# ESP32FishLightBoard.net
KiCad netlist of a schematic drawn in EAGLE
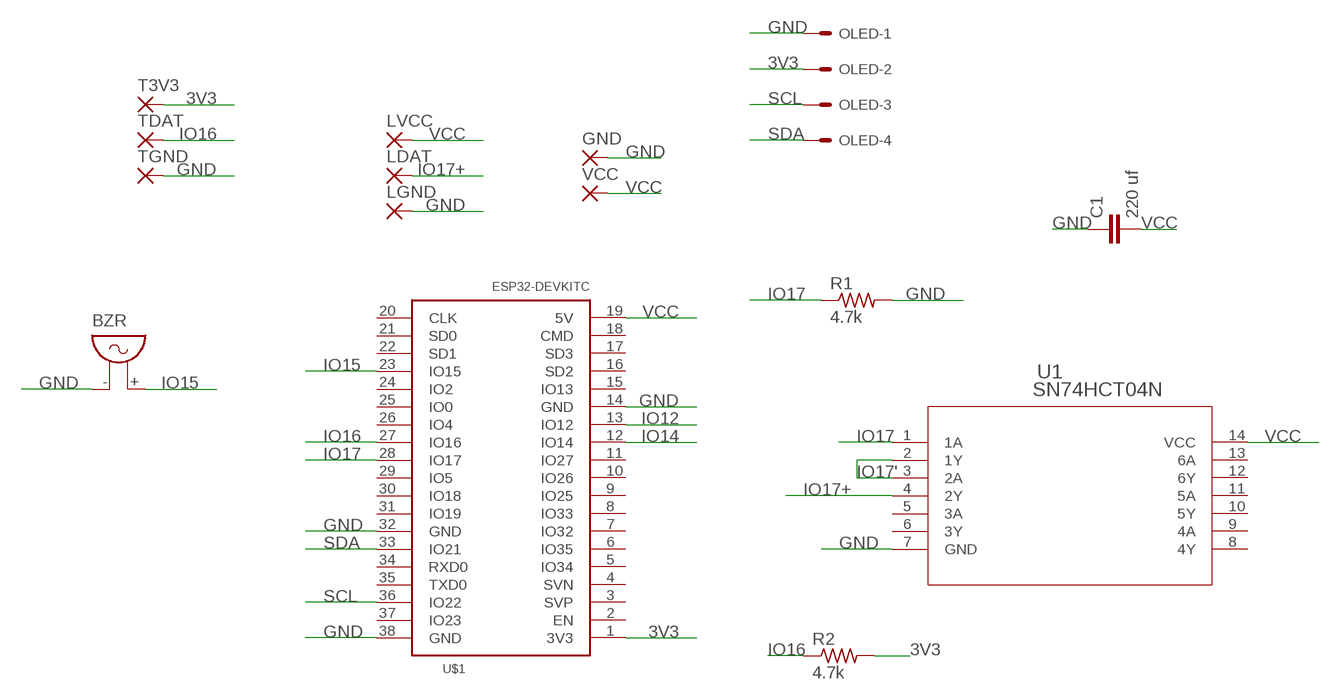
[diagram p0: schematic, sheet 1]

(export (version "E")
  (design (tool "Eeschema 10.0.6"))
  (components
    (comp (ref "BZR")
      (value "F/QMX")
      (footprint "eagle-import:F_QMX")
      (libsource (lib "eagle-import") (part "F/QMX"))
    )
    (comp (ref "C1")
      (value "220 uf")
      (footprint "eagle-import:C2.5-3")
      (libsource (lib "eagle-import") (part "C2,5-3"))
    )
    (comp (ref "GND")
      (value "WIREPAD2,54/1,0")
      (footprint "eagle-import:2,54_1,0")
      (libsource (lib "eagle-import") (part "WIREPAD2,54/1,0"))
    )
    (comp (ref "LDAT")
      (value "WIREPAD2,54/1,0")
      (footprint "eagle-import:2,54_1,0")
      (libsource (lib "eagle-import") (part "WIREPAD2,54/1,0"))
    )
    (comp (ref "LGND")
      (value "WIREPAD2,54/1,0")
      (footprint "eagle-import:2,54_1,0")
      (libsource (lib "eagle-import") (part "WIREPAD2,54/1,0"))
    )
    (comp (ref "LVCC")
      (value "WIREPAD2,54/1,0")
      (footprint "eagle-import:2,54_1,0")
      (libsource (lib "eagle-import") (part "WIREPAD2,54/1,0"))
    )
    (comp (ref "OLED")
      (value "22-27-2041-04")
      (footprint "eagle-import:6410-04")
      (fields (field (name "MF") "MOLEX"))
      (libsource (lib "eagle-import") (part "22-?-0427-2041"))
    )
    (comp (ref "R1")
      (value "4.7k")
      (footprint "eagle-import:0805-THM")
      (libsource (lib "eagle-import") (part "FLIPFLOP-RES"))
    )
    (comp (ref "R2")
      (value "4.7k")
      (footprint "eagle-import:0805-THM")
      (libsource (lib "eagle-import") (part "FLIPFLOP-RES"))
    )
    (comp (ref "T3V3")
      (value "WIREPAD2,54/1,0")
      (footprint "eagle-import:2,54_1,0")
      (libsource (lib "eagle-import") (part "WIREPAD2,54/1,0"))
    )
    (comp (ref "TDAT")
      (value "WIREPAD2,54/1,0")
      (footprint "eagle-import:2,54_1,0")
      (libsource (lib "eagle-import") (part "WIREPAD2,54/1,0"))
    )
    (comp (ref "TGND")
      (value "WIREPAD2,54/1,0")
      (footprint "eagle-import:2,54_1,0")
      (libsource (lib "eagle-import") (part "WIREPAD2,54/1,0"))
    )
    (comp (ref "U$1")
      (value "ESP32DEVKITC-LIGHT")
      (footprint "eagle-import:ESP32-DEVKITC-LIGHT")
      (libsource (lib "eagle-import") (part "ESP32DEVKITC-LIGHT"))
    )
    (comp (ref "U1")
      (value "SN74HCT04N")
      (footprint "eagle-import:N14")
      (fields
        (field (name "GENERIC_PART_NUMBER") "SN74HCT04")
        (field (name "MANUFACTURER") "Texas Instruments")
      )
      (libsource (lib "eagle-import") (part "SN74HCT04N"))
    )
    (comp (ref "VCC")
      (value "WIREPAD2,54/1,0")
      (footprint "eagle-import:2,54_1,0")
      (libsource (lib "eagle-import") (part "WIREPAD2,54/1,0"))
    )
  )
  (nets
    (net (code "1") (name "/3V3") (class "Default")
      (node (ref "OLED") (pin "2") (pinfunction "S_2") (pintype "passive"))
      (node (ref "R2") (pin "2") (pinfunction "2_2") (pintype "passive"))
      (node (ref "T3V3") (pin "1") (pinfunction "P_1") (pintype "passive"))
      (node (ref "U$1") (pin "1") (pinfunction "3V3_1") (pintype "bidirectional"))
    )
    (net (code "2") (name "/GND") (class "Default")
      (node (ref "BZR") (pin "-") (pinfunction "1_-") (pintype "passive"))
      (node (ref "C1") (pin "1") (pinfunction "1_1") (pintype "passive"))
      (node (ref "GND") (pin "1") (pinfunction "P_1") (pintype "passive"))
      (node (ref "LGND") (pin "1") (pinfunction "P_1") (pintype "passive"))
      (node (ref "OLED") (pin "1") (pinfunction "S_1") (pintype "passive"))
      (node (ref "R1") (pin "2") (pinfunction "2_2") (pintype "passive"))
      (node (ref "TGND") (pin "1") (pinfunction "P_1") (pintype "passive"))
      (node (ref "U$1") (pin "14") (pinfunction "GND_14") (pintype "bidirectional"))
      (node (ref "U$1") (pin "32") (pinfunction "GND_32") (pintype "bidirectional"))
      (node (ref "U$1") (pin "38") (pinfunction "GND_38") (pintype "bidirectional"))
      (node (ref "U1") (pin "7") (pinfunction "GND_7") (pintype "power_in"))
    )
    (net (code "3") (name "/IO12") (class "Default")
      (node (ref "U$1") (pin "13") (pinfunction "IO12_13") (pintype "bidirectional"))
    )
    (net (code "4") (name "/IO14") (class "Default")
      (node (ref "U$1") (pin "12") (pinfunction "IO14_12") (pintype "bidirectional"))
    )
    (net (code "5") (name "/IO15") (class "Default")
      (node (ref "BZR") (pin "+") (pinfunction "2_+") (pintype "passive"))
      (node (ref "U$1") (pin "23") (pinfunction "IO15_23") (pintype "bidirectional"))
    )
    (net (code "6") (name "/IO16") (class "Default")
      (node (ref "R2") (pin "1") (pinfunction "1_1") (pintype "passive"))
      (node (ref "TDAT") (pin "1") (pinfunction "P_1") (pintype "passive"))
      (node (ref "U$1") (pin "27") (pinfunction "IO16_27") (pintype "bidirectional"))
    )
    (net (code "7") (name "/IO17") (class "Default")
      (node (ref "R1") (pin "1") (pinfunction "1_1") (pintype "passive"))
      (node (ref "U$1") (pin "28") (pinfunction "IO17_28") (pintype "bidirectional"))
      (node (ref "U1") (pin "1") (pinfunction "1A_1") (pintype "input"))
    )
    (net (code "8") (name "/IO17'") (class "Default")
      (node (ref "U1") (pin "2") (pinfunction "1Y_2") (pintype "output"))
      (node (ref "U1") (pin "3") (pinfunction "2A_3") (pintype "input"))
    )
    (net (code "9") (name "/IO17+") (class "Default")
      (node (ref "LDAT") (pin "1") (pinfunction "P_1") (pintype "passive"))
      (node (ref "U1") (pin "4") (pinfunction "2Y_4") (pintype "output"))
    )
    (net (code "10") (name "/SCL") (class "Default")
      (node (ref "OLED") (pin "3") (pinfunction "S_3") (pintype "passive"))
      (node (ref "U$1") (pin "36") (pinfunction "IO22_36") (pintype "bidirectional"))
    )
    (net (code "11") (name "/SDA") (class "Default")
      (node (ref "OLED") (pin "4") (pinfunction "S_4") (pintype "passive"))
      (node (ref "U$1") (pin "33") (pinfunction "IO21_33") (pintype "bidirectional"))
    )
    (net (code "12") (name "/VCC") (class "Default")
      (node (ref "C1") (pin "2") (pinfunction "2_2") (pintype "passive"))
      (node (ref "LVCC") (pin "1") (pinfunction "P_1") (pintype "passive"))
      (node (ref "U$1") (pin "19") (pinfunction "5V_19") (pintype "bidirectional"))
      (node (ref "U1") (pin "14") (pinfunction "VCC_14") (pintype "power_in"))
      (node (ref "VCC") (pin "1") (pinfunction "P_1") (pintype "passive"))
    )
    (net (code "13") (name "unconnected-(U$1-CLK-Pad20)") (class "Default")
      (node (ref "U$1") (pin "20") (pinfunction "CLK_20") (pintype "bidirectional"))
    )
    (net (code "14") (name "unconnected-(U$1-CMD-Pad18)") (class "Default")
      (node (ref "U$1") (pin "18") (pinfunction "CMD_18") (pintype "bidirectional"))
    )
    (net (code "15") (name "unconnected-(U$1-EN-Pad2)") (class "Default")
      (node (ref "U$1") (pin "2") (pinfunction "EN_2") (pintype "bidirectional"))
    )
    (net (code "16") (name "unconnected-(U$1-IO0-Pad25)") (class "Default")
      (node (ref "U$1") (pin "25") (pinfunction "IO0_25") (pintype "bidirectional"))
    )
    (net (code "17") (name "unconnected-(U$1-IO2-Pad24)") (class "Default")
      (node (ref "U$1") (pin "24") (pinfunction "IO2_24") (pintype "bidirectional"))
    )
    (net (code "18") (name "unconnected-(U$1-IO4-Pad26)") (class "Default")
      (node (ref "U$1") (pin "26") (pinfunction "IO4_26") (pintype "bidirectional"))
    )
    (net (code "19") (name "unconnected-(U$1-IO5-Pad29)") (class "Default")
      (node (ref "U$1") (pin "29") (pinfunction "IO5_29") (pintype "bidirectional"))
    )
    (net (code "20") (name "unconnected-(U$1-IO13-Pad15)") (class "Default")
      (node (ref "U$1") (pin "15") (pinfunction "IO13_15") (pintype "bidirectional"))
    )
    (net (code "21") (name "unconnected-(U$1-IO18-Pad30)") (class "Default")
      (node (ref "U$1") (pin "30") (pinfunction "IO18_30") (pintype "bidirectional"))
    )
    (net (code "22") (name "unconnected-(U$1-IO19-Pad31)") (class "Default")
      (node (ref "U$1") (pin "31") (pinfunction "IO19_31") (pintype "bidirectional"))
    )
    (net (code "23") (name "unconnected-(U$1-IO23-Pad37)") (class "Default")
      (node (ref "U$1") (pin "37") (pinfunction "IO23_37") (pintype "bidirectional"))
    )
    (net (code "24") (name "unconnected-(U$1-IO25-Pad9)") (class "Default")
      (node (ref "U$1") (pin "9") (pinfunction "IO25_9") (pintype "bidirectional"))
    )
    (net (code "25") (name "unconnected-(U$1-IO26-Pad10)") (class "Default")
      (node (ref "U$1") (pin "10") (pinfunction "IO26_10") (pintype "bidirectional"))
    )
    (net (code "26") (name "unconnected-(U$1-IO27-Pad11)") (class "Default")
      (node (ref "U$1") (pin "11") (pinfunction "IO27_11") (pintype "bidirectional"))
    )
    (net (code "27") (name "unconnected-(U$1-IO32-Pad7)") (class "Default")
      (node (ref "U$1") (pin "7") (pinfunction "IO32_7") (pintype "bidirectional"))
    )
    (net (code "28") (name "unconnected-(U$1-IO33-Pad8)") (class "Default")
      (node (ref "U$1") (pin "8") (pinfunction "IO33_8") (pintype "bidirectional"))
    )
    (net (code "29") (name "unconnected-(U$1-IO34-Pad5)") (class "Default")
      (node (ref "U$1") (pin "5") (pinfunction "IO34_5") (pintype "bidirectional"))
    )
    (net (code "30") (name "unconnected-(U$1-IO35-Pad6)") (class "Default")
      (node (ref "U$1") (pin "6") (pinfunction "IO35_6") (pintype "bidirectional"))
    )
    (net (code "31") (name "unconnected-(U$1-RXD0-Pad34)") (class "Default")
      (node (ref "U$1") (pin "34") (pinfunction "RXD0_34") (pintype "bidirectional"))
    )
    (net (code "32") (name "unconnected-(U$1-SD0-Pad21)") (class "Default")
      (node (ref "U$1") (pin "21") (pinfunction "SD0_21") (pintype "bidirectional"))
    )
    (net (code "33") (name "unconnected-(U$1-SD1-Pad22)") (class "Default")
      (node (ref "U$1") (pin "22") (pinfunction "SD1_22") (pintype "bidirectional"))
    )
    (net (code "34") (name "unconnected-(U$1-SD2-Pad16)") (class "Default")
      (node (ref "U$1") (pin "16") (pinfunction "SD2_16") (pintype "bidirectional"))
    )
    (net (code "35") (name "unconnected-(U$1-SD3-Pad17)") (class "Default")
      (node (ref "U$1") (pin "17") (pinfunction "SD3_17") (pintype "bidirectional"))
    )
    (net (code "36") (name "unconnected-(U$1-SVN-Pad4)") (class "Default")
      (node (ref "U$1") (pin "4") (pinfunction "SVN_4") (pintype "bidirectional"))
    )
    (net (code "37") (name "unconnected-(U$1-SVP-Pad3)") (class "Default")
      (node (ref "U$1") (pin "3") (pinfunction "SVP_3") (pintype "bidirectional"))
    )
    (net (code "38") (name "unconnected-(U$1-TXD0-Pad35)") (class "Default")
      (node (ref "U$1") (pin "35") (pinfunction "TXD0_35") (pintype "bidirectional"))
    )
    (net (code "39") (name "unconnected-(U1-3A-Pad5)") (class "Default")
      (node (ref "U1") (pin "5") (pinfunction "3A_5") (pintype "input"))
    )
    (net (code "40") (name "unconnected-(U1-3Y-Pad6)") (class "Default")
      (node (ref "U1") (pin "6") (pinfunction "3Y_6") (pintype "output"))
    )
    (net (code "41") (name "unconnected-(U1-4A-Pad9)") (class "Default")
      (node (ref "U1") (pin "9") (pinfunction "4A_9") (pintype "input"))
    )
    (net (code "42") (name "unconnected-(U1-4Y-Pad8)") (class "Default")
      (node (ref "U1") (pin "8") (pinfunction "4Y_8") (pintype "output"))
    )
    (net (code "43") (name "unconnected-(U1-5A-Pad11)") (class "Default")
      (node (ref "U1") (pin "11") (pinfunction "5A_11") (pintype "input"))
    )
    (net (code "44") (name "unconnected-(U1-5Y-Pad10)") (class "Default")
      (node (ref "U1") (pin "10") (pinfunction "5Y_10") (pintype "output"))
    )
    (net (code "45") (name "unconnected-(U1-6A-Pad13)") (class "Default")
      (node (ref "U1") (pin "13") (pinfunction "6A_13") (pintype "input"))
    )
    (net (code "46") (name "unconnected-(U1-6Y-Pad12)") (class "Default")
      (node (ref "U1") (pin "12") (pinfunction "6Y_12") (pintype "output"))
    )
  )
)
